# SCH_PLU-Piano-v1_0_2024-04-26.net
KiCad netlist of a schematic drawn in EasyEDA
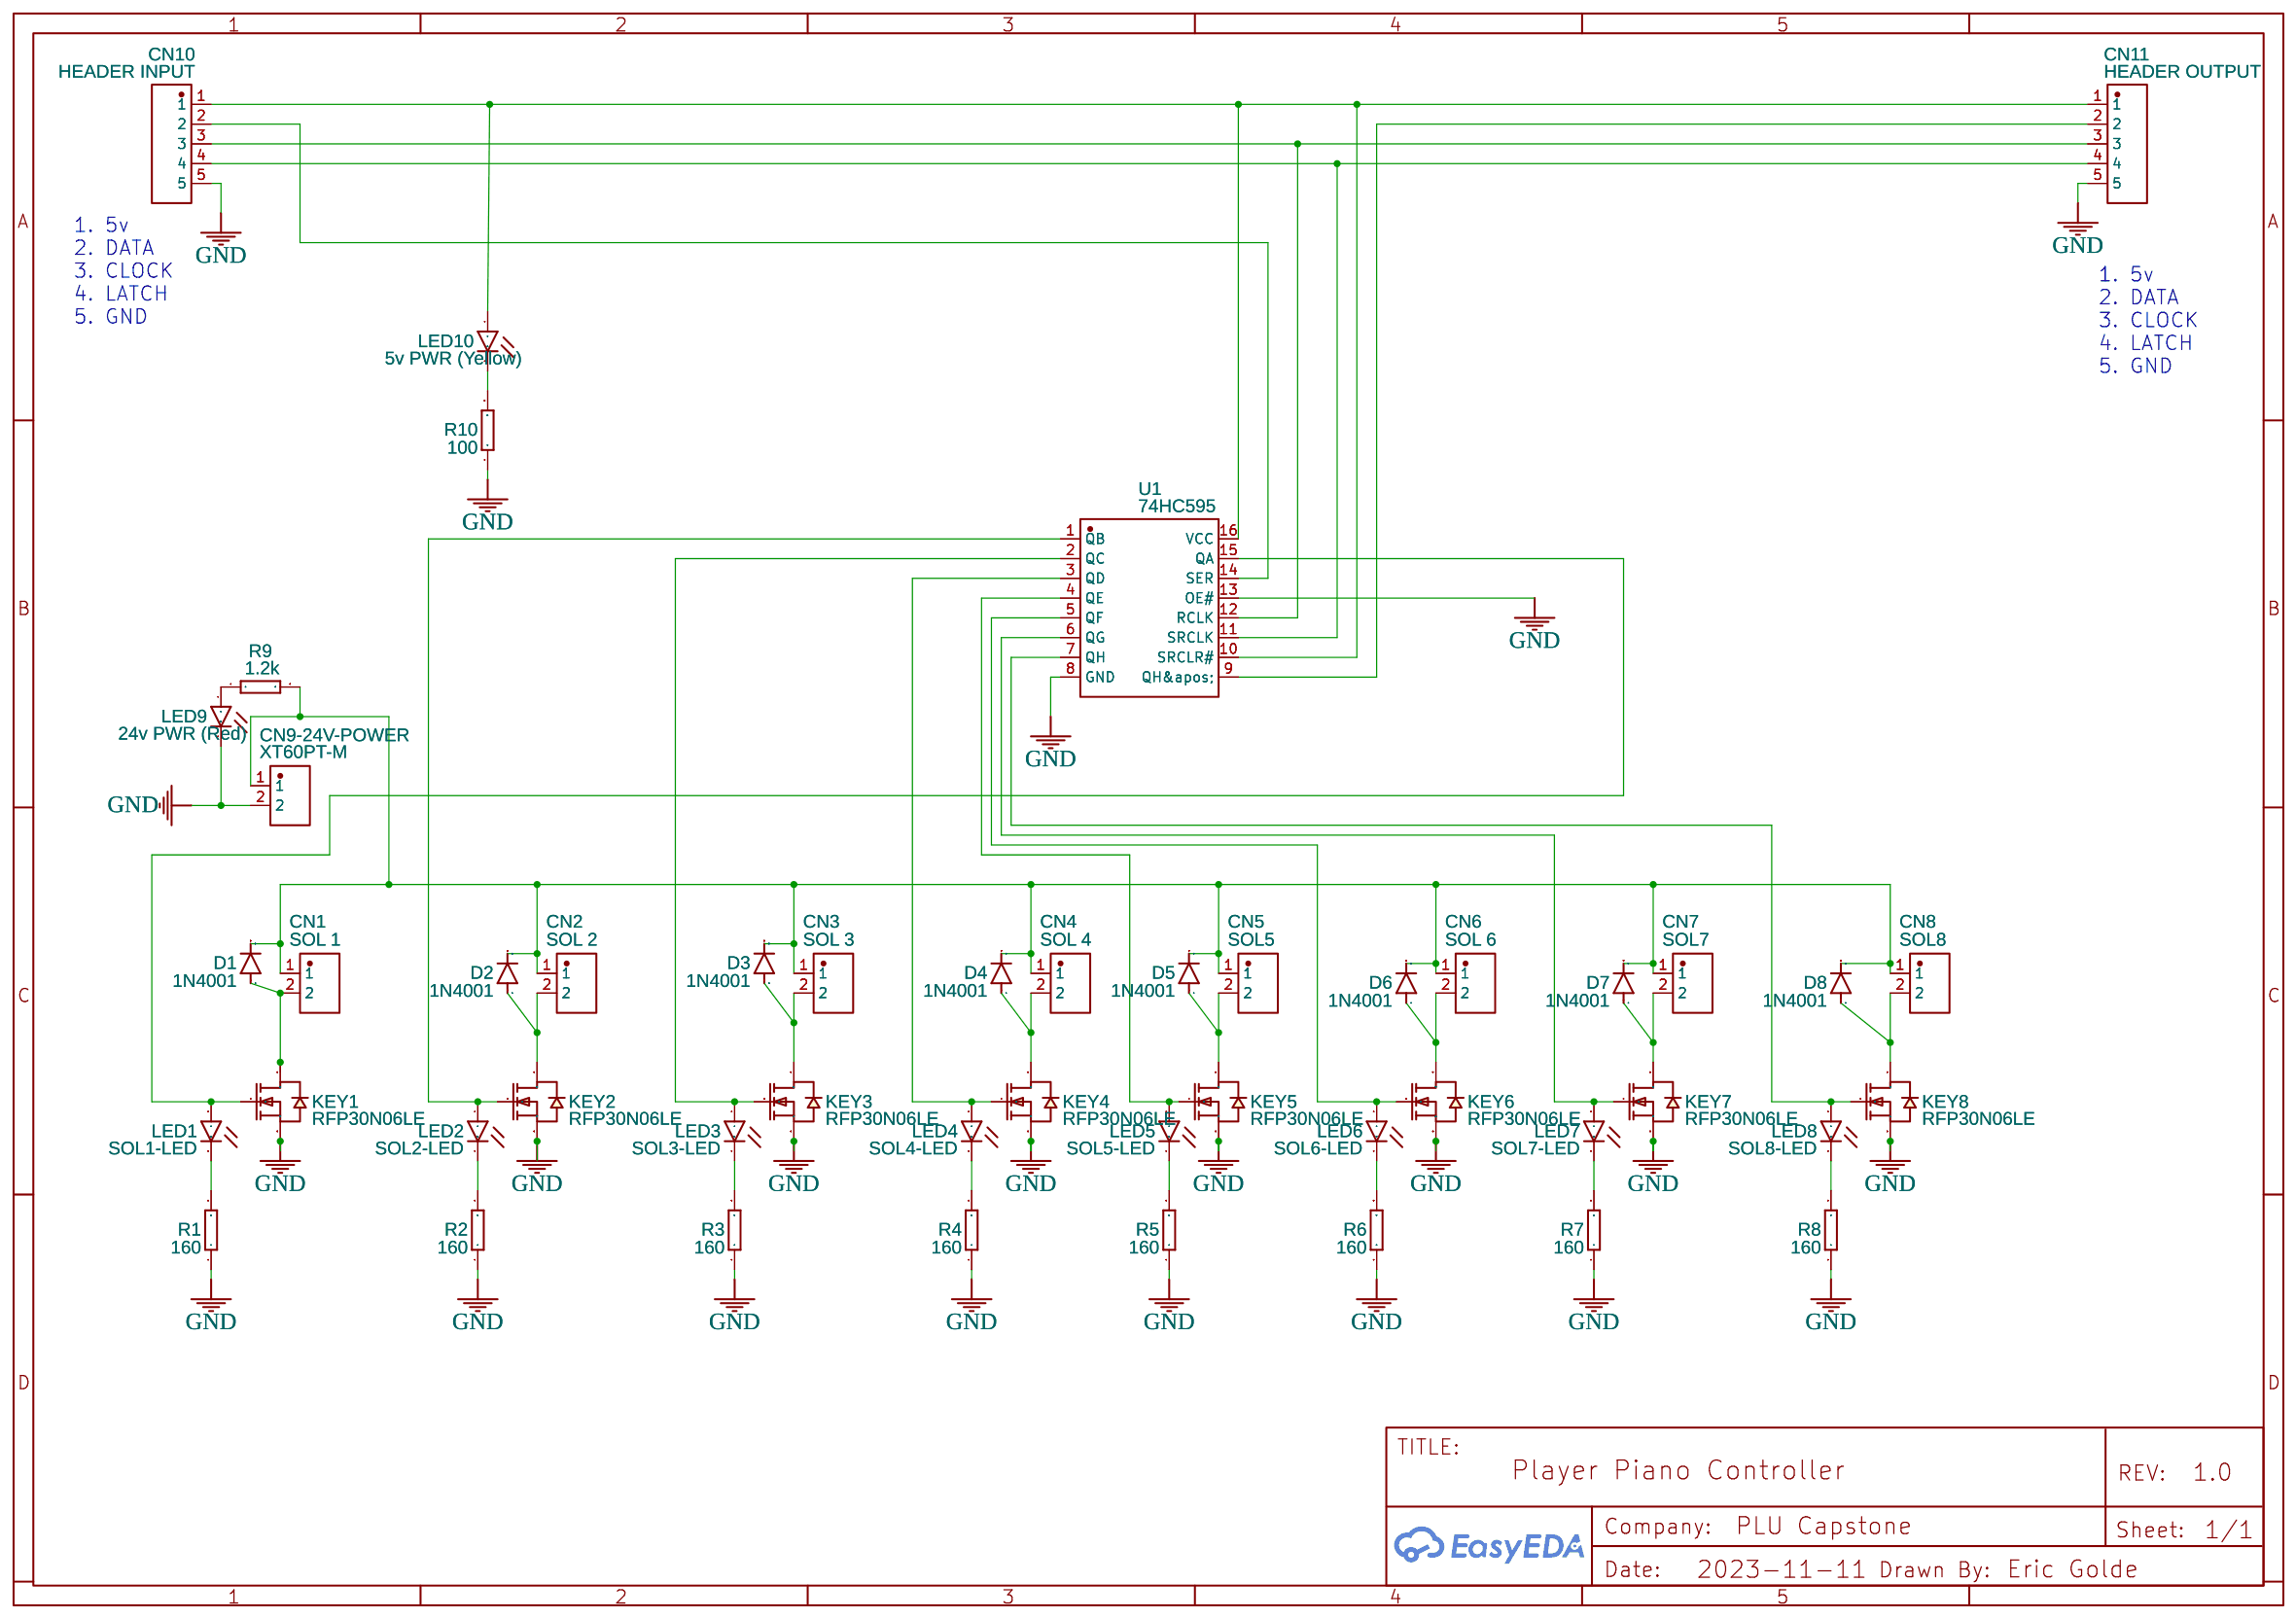
[diagram p0: schematic sheet]

(export (version "E")
  (design (tool "Eeschema 10.0.6"))
  (components
    (comp (ref "CN1")
      (value "SOL 1")
      (fields (field (name "Manufacturer Part") "VH2-Header2"))
      (libsource (lib "") (part "VH2-HEADER2"))
    )
    (comp (ref "CN2")
      (value "SOL 2")
      (fields (field (name "Manufacturer Part") "VH2-Header2"))
      (libsource (lib "") (part "VH2-HEADER2"))
    )
    (comp (ref "CN3")
      (value "SOL 3")
      (fields (field (name "Manufacturer Part") "VH2-Header2"))
      (libsource (lib "") (part "VH2-HEADER2"))
    )
    (comp (ref "CN4")
      (value "SOL 4")
      (fields (field (name "Manufacturer Part") "VH2-Header2"))
      (libsource (lib "") (part "VH2-HEADER2"))
    )
    (comp (ref "CN5")
      (value "SOL5")
      (fields (field (name "Manufacturer Part") "VH2-Header2"))
      (libsource (lib "") (part "VH2-HEADER2"))
    )
    (comp (ref "CN6")
      (value "SOL 6")
      (fields (field (name "Manufacturer Part") "VH2-Header2"))
      (libsource (lib "") (part "VH2-HEADER2"))
    )
    (comp (ref "CN7")
      (value "SOL7")
      (fields (field (name "Manufacturer Part") "VH2-Header2"))
      (libsource (lib "") (part "VH2-HEADER2"))
    )
    (comp (ref "CN8")
      (value "SOL8")
      (fields (field (name "Manufacturer Part") "VH2-Header2"))
      (libsource (lib "") (part "VH2-HEADER2"))
    )
    (comp (ref "CN9-24V-POWER") (value "XT60PT-M") (libsource (lib "") (part "XT60PT-M")))
    (comp (ref "CN10")
      (value "HEADER INPUT")
      (fields (field (name "Manufacturer Part") "Header5"))
      (libsource (lib "") (part "HEADER5"))
    )
    (comp (ref "CN11")
      (value "HEADER OUTPUT")
      (fields (field (name "Manufacturer Part") "Header5"))
      (libsource (lib "") (part "HEADER5_1"))
    )
    (comp (ref "D1") (value "1N4001") (libsource (lib "") (part "DIODE1N4148")))
    (comp (ref "D2") (value "1N4001") (libsource (lib "") (part "DIODE1N4148")))
    (comp (ref "D3") (value "1N4001") (libsource (lib "") (part "DIODE1N4148")))
    (comp (ref "D4") (value "1N4001") (libsource (lib "") (part "DIODE1N4148")))
    (comp (ref "D5") (value "1N4001") (libsource (lib "") (part "DIODE1N4148")))
    (comp (ref "D6") (value "1N4001") (libsource (lib "") (part "DIODE1N4148")))
    (comp (ref "D7") (value "1N4001") (libsource (lib "") (part "DIODE1N4148")))
    (comp (ref "D8") (value "1N4001") (libsource (lib "") (part "DIODE1N4148")))
    (comp (ref "KEY1")
      (value "RFP30N06LE")
      (fields (field (name "Manufacturer Part") "RFP30N06LE-VB") (field (name "Manufacturer") "VBsemi(微碧)"))
      (libsource (lib "") (part "RFP30N06LE"))
    )
    (comp (ref "KEY2")
      (value "RFP30N06LE")
      (fields (field (name "Manufacturer Part") "RFP30N06LE-VB") (field (name "Manufacturer") "VBsemi(微碧)"))
      (libsource (lib "") (part "RFP30N06LE"))
    )
    (comp (ref "KEY3")
      (value "RFP30N06LE")
      (fields (field (name "Manufacturer Part") "RFP30N06LE-VB") (field (name "Manufacturer") "VBsemi(微碧)"))
      (libsource (lib "") (part "RFP30N06LE"))
    )
    (comp (ref "KEY4")
      (value "RFP30N06LE")
      (fields (field (name "Manufacturer Part") "RFP30N06LE-VB") (field (name "Manufacturer") "VBsemi(微碧)"))
      (libsource (lib "") (part "RFP30N06LE"))
    )
    (comp (ref "KEY5")
      (value "RFP30N06LE")
      (fields (field (name "Manufacturer Part") "RFP30N06LE-VB") (field (name "Manufacturer") "VBsemi(微碧)"))
      (libsource (lib "") (part "RFP30N06LE"))
    )
    (comp (ref "KEY6")
      (value "RFP30N06LE")
      (fields (field (name "Manufacturer Part") "RFP30N06LE-VB") (field (name "Manufacturer") "VBsemi(微碧)"))
      (libsource (lib "") (part "RFP30N06LE"))
    )
    (comp (ref "KEY7")
      (value "RFP30N06LE")
      (fields (field (name "Manufacturer Part") "RFP30N06LE-VB") (field (name "Manufacturer") "VBsemi(微碧)"))
      (libsource (lib "") (part "RFP30N06LE"))
    )
    (comp (ref "KEY8")
      (value "RFP30N06LE")
      (fields (field (name "Manufacturer Part") "RFP30N06LE-VB") (field (name "Manufacturer") "VBsemi(微碧)"))
      (libsource (lib "") (part "RFP30N06LE"))
    )
    (comp (ref "LED1") (value "SOL1-LED") (libsource (lib "") (part "LED-IR-THRUTSAL6100")))
    (comp (ref "LED2") (value "SOL2-LED") (libsource (lib "") (part "LED-IR-THRUTSAL6100")))
    (comp (ref "LED3") (value "SOL3-LED") (libsource (lib "") (part "LED-IR-THRUTSAL6100")))
    (comp (ref "LED4") (value "SOL4-LED") (libsource (lib "") (part "LED-IR-THRUTSAL6100")))
    (comp (ref "LED5") (value "SOL5-LED") (libsource (lib "") (part "LED-IR-THRUTSAL6100")))
    (comp (ref "LED6") (value "SOL6-LED") (libsource (lib "") (part "LED-IR-THRUTSAL6100")))
    (comp (ref "LED7") (value "SOL7-LED") (libsource (lib "") (part "LED-IR-THRUTSAL6100")))
    (comp (ref "LED8") (value "SOL8-LED") (libsource (lib "") (part "LED-IR-THRUTSAL6100")))
    (comp (ref "LED9") (value "24v PWR (Red)") (libsource (lib "") (part "LED-IR-THRUTSAL6100")))
    (comp (ref "LED10") (value "5v PWR (Yellow)") (libsource (lib "") (part "LED-IR-THRUTSAL6100")))
    (comp (ref "R1") (value "160") (libsource (lib "") (part "RESISTOR")))
    (comp (ref "R2") (value "160") (libsource (lib "") (part "RESISTOR")))
    (comp (ref "R3") (value "160") (libsource (lib "") (part "RESISTOR")))
    (comp (ref "R4") (value "160") (libsource (lib "") (part "RESISTOR")))
    (comp (ref "R5") (value "160") (libsource (lib "") (part "RESISTOR")))
    (comp (ref "R6") (value "160") (libsource (lib "") (part "RESISTOR")))
    (comp (ref "R7") (value "160") (libsource (lib "") (part "RESISTOR")))
    (comp (ref "R8") (value "160") (libsource (lib "") (part "RESISTOR")))
    (comp (ref "R9") (value "1.2k") (libsource (lib "") (part "RESISTOR_1")))
    (comp (ref "R10") (value "100") (libsource (lib "") (part "RESISTOR")))
    (comp (ref "U1")
      (value "74HC595")
      (fields (field (name "Manufacturer Part") "SN74HC595NE4") (field (name "Manufacturer") "TI(德州仪器)"))
      (libsource (lib "") (part "SN74HC595NE4"))
    )
  )
  (nets
    (net (code "1") (name "GND") (class "Default")
      (node (ref "CN10") (pin "5") (pinfunction "5_5") (pintype "unspecified"))
      (node (ref "CN11") (pin "5") (pinfunction "5_5") (pintype "unspecified"))
      (node (ref "CN9-24V-POWER") (pin "2") (pinfunction "2_2") (pintype "unspecified"))
      (node (ref "KEY1") (pin "3") (pinfunction "S_3") (pintype "unspecified"))
      (node (ref "KEY2") (pin "3") (pinfunction "S_3") (pintype "unspecified"))
      (node (ref "KEY3") (pin "3") (pinfunction "S_3") (pintype "unspecified"))
      (node (ref "KEY4") (pin "3") (pinfunction "S_3") (pintype "unspecified"))
      (node (ref "KEY5") (pin "3") (pinfunction "S_3") (pintype "unspecified"))
      (node (ref "KEY6") (pin "3") (pinfunction "S_3") (pintype "unspecified"))
      (node (ref "KEY7") (pin "3") (pinfunction "S_3") (pintype "unspecified"))
      (node (ref "KEY8") (pin "3") (pinfunction "S_3") (pintype "unspecified"))
      (node (ref "LED9") (pin "K") (pinfunction "C_K") (pintype "unspecified"))
      (node (ref "R1") (pin "1") (pinfunction "1_1") (pintype "unspecified"))
      (node (ref "R10") (pin "1") (pinfunction "1_1") (pintype "unspecified"))
      (node (ref "R2") (pin "1") (pinfunction "1_1") (pintype "unspecified"))
      (node (ref "R3") (pin "1") (pinfunction "1_1") (pintype "unspecified"))
      (node (ref "R4") (pin "1") (pinfunction "1_1") (pintype "unspecified"))
      (node (ref "R5") (pin "1") (pinfunction "1_1") (pintype "unspecified"))
      (node (ref "R6") (pin "1") (pinfunction "1_1") (pintype "unspecified"))
      (node (ref "R7") (pin "1") (pinfunction "1_1") (pintype "unspecified"))
      (node (ref "R8") (pin "1") (pinfunction "1_1") (pintype "unspecified"))
      (node (ref "U1") (pin "13") (pinfunction "OE#_13") (pintype "unspecified"))
      (node (ref "U1") (pin "8") (pinfunction "GND_8") (pintype "unspecified"))
    )
    (net (code "2") (name "Net-(CN1-Pad1)") (class "Default")
      (node (ref "CN1") (pin "1") (pinfunction "1_1") (pintype "unspecified"))
      (node (ref "CN2") (pin "1") (pinfunction "1_1") (pintype "unspecified"))
      (node (ref "CN3") (pin "1") (pinfunction "1_1") (pintype "unspecified"))
      (node (ref "CN4") (pin "1") (pinfunction "1_1") (pintype "unspecified"))
      (node (ref "CN5") (pin "1") (pinfunction "1_1") (pintype "unspecified"))
      (node (ref "CN6") (pin "1") (pinfunction "1_1") (pintype "unspecified"))
      (node (ref "CN7") (pin "1") (pinfunction "1_1") (pintype "unspecified"))
      (node (ref "CN8") (pin "1") (pinfunction "1_1") (pintype "unspecified"))
      (node (ref "CN9-24V-POWER") (pin "1") (pinfunction "1_1") (pintype "unspecified"))
      (node (ref "D1") (pin "C") (pinfunction "C_C") (pintype "unspecified"))
      (node (ref "D2") (pin "C") (pinfunction "C_C") (pintype "unspecified"))
      (node (ref "D3") (pin "C") (pinfunction "C_C") (pintype "unspecified"))
      (node (ref "D4") (pin "C") (pinfunction "C_C") (pintype "unspecified"))
      (node (ref "D5") (pin "C") (pinfunction "C_C") (pintype "unspecified"))
      (node (ref "D6") (pin "C") (pinfunction "C_C") (pintype "unspecified"))
      (node (ref "D7") (pin "C") (pinfunction "C_C") (pintype "unspecified"))
      (node (ref "D8") (pin "C") (pinfunction "C_C") (pintype "unspecified"))
      (node (ref "R9") (pin "2") (pinfunction "2_2") (pintype "unspecified"))
    )
    (net (code "3") (name "Net-(KEY1-D)") (class "Default")
      (node (ref "CN1") (pin "2") (pinfunction "2_2") (pintype "unspecified"))
      (node (ref "D1") (pin "A") (pinfunction "A_A") (pintype "unspecified"))
      (node (ref "KEY1") (pin "2") (pinfunction "D_2") (pintype "unspecified"))
    )
    (net (code "4") (name "Net-(KEY1-G)") (class "Default")
      (node (ref "KEY1") (pin "1") (pinfunction "G_1") (pintype "unspecified"))
      (node (ref "LED1") (pin "A") (pinfunction "A_A") (pintype "unspecified"))
      (node (ref "U1") (pin "15") (pinfunction "QA_15") (pintype "unspecified"))
    )
    (net (code "5") (name "Net-(KEY2-D)") (class "Default")
      (node (ref "CN2") (pin "2") (pinfunction "2_2") (pintype "unspecified"))
      (node (ref "D2") (pin "A") (pinfunction "A_A") (pintype "unspecified"))
      (node (ref "KEY2") (pin "2") (pinfunction "D_2") (pintype "unspecified"))
    )
    (net (code "6") (name "Net-(KEY2-G)") (class "Default")
      (node (ref "KEY2") (pin "1") (pinfunction "G_1") (pintype "unspecified"))
      (node (ref "LED2") (pin "A") (pinfunction "A_A") (pintype "unspecified"))
      (node (ref "U1") (pin "1") (pinfunction "QB_1") (pintype "unspecified"))
    )
    (net (code "7") (name "Net-(KEY3-D)") (class "Default")
      (node (ref "CN3") (pin "2") (pinfunction "2_2") (pintype "unspecified"))
      (node (ref "D3") (pin "A") (pinfunction "A_A") (pintype "unspecified"))
      (node (ref "KEY3") (pin "2") (pinfunction "D_2") (pintype "unspecified"))
    )
    (net (code "8") (name "Net-(KEY3-G)") (class "Default")
      (node (ref "KEY3") (pin "1") (pinfunction "G_1") (pintype "unspecified"))
      (node (ref "LED3") (pin "A") (pinfunction "A_A") (pintype "unspecified"))
      (node (ref "U1") (pin "2") (pinfunction "QC_2") (pintype "unspecified"))
    )
    (net (code "9") (name "Net-(KEY4-D)") (class "Default")
      (node (ref "CN4") (pin "2") (pinfunction "2_2") (pintype "unspecified"))
      (node (ref "D4") (pin "A") (pinfunction "A_A") (pintype "unspecified"))
      (node (ref "KEY4") (pin "2") (pinfunction "D_2") (pintype "unspecified"))
    )
    (net (code "10") (name "Net-(KEY4-G)") (class "Default")
      (node (ref "KEY4") (pin "1") (pinfunction "G_1") (pintype "unspecified"))
      (node (ref "LED4") (pin "A") (pinfunction "A_A") (pintype "unspecified"))
      (node (ref "U1") (pin "3") (pinfunction "QD_3") (pintype "unspecified"))
    )
    (net (code "11") (name "Net-(KEY5-D)") (class "Default")
      (node (ref "CN5") (pin "2") (pinfunction "2_2") (pintype "unspecified"))
      (node (ref "D5") (pin "A") (pinfunction "A_A") (pintype "unspecified"))
      (node (ref "KEY5") (pin "2") (pinfunction "D_2") (pintype "unspecified"))
    )
    (net (code "12") (name "Net-(KEY5-G)") (class "Default")
      (node (ref "KEY5") (pin "1") (pinfunction "G_1") (pintype "unspecified"))
      (node (ref "LED5") (pin "A") (pinfunction "A_A") (pintype "unspecified"))
      (node (ref "U1") (pin "4") (pinfunction "QE_4") (pintype "unspecified"))
    )
    (net (code "13") (name "Net-(KEY6-D)") (class "Default")
      (node (ref "CN6") (pin "2") (pinfunction "2_2") (pintype "unspecified"))
      (node (ref "D6") (pin "A") (pinfunction "A_A") (pintype "unspecified"))
      (node (ref "KEY6") (pin "2") (pinfunction "D_2") (pintype "unspecified"))
    )
    (net (code "14") (name "Net-(KEY6-G)") (class "Default")
      (node (ref "KEY6") (pin "1") (pinfunction "G_1") (pintype "unspecified"))
      (node (ref "LED6") (pin "A") (pinfunction "A_A") (pintype "unspecified"))
      (node (ref "U1") (pin "5") (pinfunction "QF_5") (pintype "unspecified"))
    )
    (net (code "15") (name "Net-(KEY7-D)") (class "Default")
      (node (ref "CN7") (pin "2") (pinfunction "2_2") (pintype "unspecified"))
      (node (ref "D7") (pin "A") (pinfunction "A_A") (pintype "unspecified"))
      (node (ref "KEY7") (pin "2") (pinfunction "D_2") (pintype "unspecified"))
    )
    (net (code "16") (name "Net-(KEY7-G)") (class "Default")
      (node (ref "KEY7") (pin "1") (pinfunction "G_1") (pintype "unspecified"))
      (node (ref "LED7") (pin "A") (pinfunction "A_A") (pintype "unspecified"))
      (node (ref "U1") (pin "6") (pinfunction "QG_6") (pintype "unspecified"))
    )
    (net (code "17") (name "Net-(KEY8-D)") (class "Default")
      (node (ref "CN8") (pin "2") (pinfunction "2_2") (pintype "unspecified"))
      (node (ref "D8") (pin "A") (pinfunction "A_A") (pintype "unspecified"))
      (node (ref "KEY8") (pin "2") (pinfunction "D_2") (pintype "unspecified"))
    )
    (net (code "18") (name "Net-(KEY8-G)") (class "Default")
      (node (ref "KEY8") (pin "1") (pinfunction "G_1") (pintype "unspecified"))
      (node (ref "LED8") (pin "A") (pinfunction "A_A") (pintype "unspecified"))
      (node (ref "U1") (pin "7") (pinfunction "QH_7") (pintype "unspecified"))
    )
    (net (code "19") (name "Net-(LED1-C)") (class "Default")
      (node (ref "LED1") (pin "K") (pinfunction "C_K") (pintype "unspecified"))
      (node (ref "R1") (pin "2") (pinfunction "2_2") (pintype "unspecified"))
    )
    (net (code "20") (name "Net-(LED2-C)") (class "Default")
      (node (ref "LED2") (pin "K") (pinfunction "C_K") (pintype "unspecified"))
      (node (ref "R2") (pin "2") (pinfunction "2_2") (pintype "unspecified"))
    )
    (net (code "21") (name "Net-(LED3-C)") (class "Default")
      (node (ref "LED3") (pin "K") (pinfunction "C_K") (pintype "unspecified"))
      (node (ref "R3") (pin "2") (pinfunction "2_2") (pintype "unspecified"))
    )
    (net (code "22") (name "Net-(LED4-C)") (class "Default")
      (node (ref "LED4") (pin "K") (pinfunction "C_K") (pintype "unspecified"))
      (node (ref "R4") (pin "2") (pinfunction "2_2") (pintype "unspecified"))
    )
    (net (code "23") (name "Net-(LED5-C)") (class "Default")
      (node (ref "LED5") (pin "K") (pinfunction "C_K") (pintype "unspecified"))
      (node (ref "R5") (pin "2") (pinfunction "2_2") (pintype "unspecified"))
    )
    (net (code "24") (name "Net-(LED6-C)") (class "Default")
      (node (ref "LED6") (pin "K") (pinfunction "C_K") (pintype "unspecified"))
      (node (ref "R6") (pin "2") (pinfunction "2_2") (pintype "unspecified"))
    )
    (net (code "25") (name "Net-(LED7-C)") (class "Default")
      (node (ref "LED7") (pin "K") (pinfunction "C_K") (pintype "unspecified"))
      (node (ref "R7") (pin "2") (pinfunction "2_2") (pintype "unspecified"))
    )
    (net (code "26") (name "Net-(LED8-C)") (class "Default")
      (node (ref "LED8") (pin "K") (pinfunction "C_K") (pintype "unspecified"))
      (node (ref "R8") (pin "2") (pinfunction "2_2") (pintype "unspecified"))
    )
    (net (code "27") (name "Net-(LED9-PadA)") (class "Default")
      (node (ref "LED9") (pin "A") (pinfunction "A_A") (pintype "unspecified"))
      (node (ref "R9") (pin "1") (pinfunction "1_1") (pintype "unspecified"))
    )
    (net (code "28") (name "Net-(LED10-C)") (class "Default")
      (node (ref "LED10") (pin "K") (pinfunction "C_K") (pintype "unspecified"))
      (node (ref "R10") (pin "2") (pinfunction "2_2") (pintype "unspecified"))
    )
    (net (code "29") (name "Net-(U1-QH&apos;)") (class "Default")
      (node (ref "CN11") (pin "2") (pinfunction "2_2") (pintype "unspecified"))
      (node (ref "U1") (pin "9") (pinfunction "QH&apos;_9") (pintype "unspecified"))
    )
    (net (code "30") (name "Net-(U1-RCLK)") (class "Default")
      (node (ref "CN10") (pin "3") (pinfunction "3_3") (pintype "unspecified"))
      (node (ref "CN11") (pin "3") (pinfunction "3_3") (pintype "unspecified"))
      (node (ref "U1") (pin "12") (pinfunction "RCLK_12") (pintype "unspecified"))
    )
    (net (code "31") (name "Net-(U1-SER)") (class "Default")
      (node (ref "CN10") (pin "2") (pinfunction "2_2") (pintype "unspecified"))
      (node (ref "U1") (pin "14") (pinfunction "SER_14") (pintype "unspecified"))
    )
    (net (code "32") (name "Net-(U1-SRCLK)") (class "Default")
      (node (ref "CN10") (pin "4") (pinfunction "4_4") (pintype "unspecified"))
      (node (ref "CN11") (pin "4") (pinfunction "4_4") (pintype "unspecified"))
      (node (ref "U1") (pin "11") (pinfunction "SRCLK_11") (pintype "unspecified"))
    )
    (net (code "33") (name "Net-(U1-SRCLR#)") (class "Default")
      (node (ref "CN10") (pin "1") (pinfunction "1_1") (pintype "unspecified"))
      (node (ref "CN11") (pin "1") (pinfunction "1_1") (pintype "unspecified"))
      (node (ref "LED10") (pin "A") (pinfunction "A_A") (pintype "unspecified"))
      (node (ref "U1") (pin "10") (pinfunction "SRCLR#_10") (pintype "unspecified"))
      (node (ref "U1") (pin "16") (pinfunction "VCC_16") (pintype "unspecified"))
    )
  )
)
